# spio.net
KiCad netlist of a schematic drawn in EAGLE
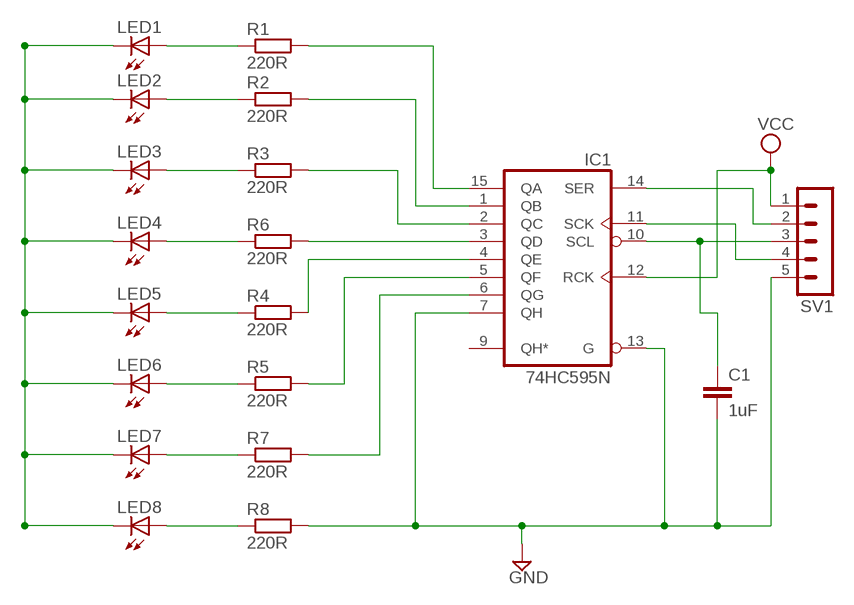
[diagram p0: schematic, sheet 1]

(export (version "E")
  (design (tool "Eeschema 10.0.6"))
  (components
    (comp (ref "C1")
      (value "1uF")
      (footprint "eagle-import:C025-024X044")
      (libsource (lib "eagle-import") (part "C-EU025-024X044"))
    )
    (comp (ref "IC1")
      (value "74HC595N")
      (footprint "eagle-import:DIL16")
      (libsource (lib "eagle-import") (part "74595NHC"))
    )
    (comp (ref "LED1")
      (value "LED5MM")
      (footprint "eagle-import:LED5MM")
      (libsource (lib "eagle-import") (part "LED5MM"))
    )
    (comp (ref "LED2")
      (value "LED5MM")
      (footprint "eagle-import:LED5MM")
      (libsource (lib "eagle-import") (part "LED5MM"))
    )
    (comp (ref "LED3")
      (value "LED5MM")
      (footprint "eagle-import:LED5MM")
      (libsource (lib "eagle-import") (part "LED5MM"))
    )
    (comp (ref "LED4")
      (value "LED5MM")
      (footprint "eagle-import:LED5MM")
      (libsource (lib "eagle-import") (part "LED5MM"))
    )
    (comp (ref "LED5")
      (value "LED5MM")
      (footprint "eagle-import:LED5MM")
      (libsource (lib "eagle-import") (part "LED5MM"))
    )
    (comp (ref "LED6")
      (value "LED5MM")
      (footprint "eagle-import:LED5MM")
      (libsource (lib "eagle-import") (part "LED5MM"))
    )
    (comp (ref "LED7")
      (value "LED5MM")
      (footprint "eagle-import:LED5MM")
      (libsource (lib "eagle-import") (part "LED5MM"))
    )
    (comp (ref "LED8")
      (value "LED5MM")
      (footprint "eagle-import:LED5MM")
      (libsource (lib "eagle-import") (part "LED5MM"))
    )
    (comp (ref "R1")
      (value "220R")
      (footprint "eagle-import:0204V")
      (libsource (lib "eagle-import") (part "R-EU_0204/2V"))
    )
    (comp (ref "R2")
      (value "220R")
      (footprint "eagle-import:0204V")
      (libsource (lib "eagle-import") (part "R-EU_0204/2V"))
    )
    (comp (ref "R3")
      (value "220R")
      (footprint "eagle-import:0204V")
      (libsource (lib "eagle-import") (part "R-EU_0204/2V"))
    )
    (comp (ref "R4")
      (value "220R")
      (footprint "eagle-import:0204V")
      (libsource (lib "eagle-import") (part "R-EU_0204/2V"))
    )
    (comp (ref "R5")
      (value "220R")
      (footprint "eagle-import:0204V")
      (libsource (lib "eagle-import") (part "R-EU_0204/2V"))
    )
    (comp (ref "R6")
      (value "220R")
      (footprint "eagle-import:0204V")
      (libsource (lib "eagle-import") (part "R-EU_0204/2V"))
    )
    (comp (ref "R7")
      (value "220R")
      (footprint "eagle-import:0204V")
      (libsource (lib "eagle-import") (part "R-EU_0204/2V"))
    )
    (comp (ref "R8")
      (value "220R")
      (footprint "eagle-import:0204V")
      (libsource (lib "eagle-import") (part "R-EU_0204/2V"))
    )
    (comp (ref "SV1")
      (value "MA05-1")
      (footprint "eagle-import:MA05-1")
      (libsource (lib "eagle-import") (part "MA05-1"))
    )
  )
  (nets
    (net (code "1") (name "GND") (class "Default")
      (node (ref "C1") (pin "2") (pinfunction "2_2") (pintype "passive"))
      (node (ref "IC1") (pin "13") (pinfunction "G_13") (pintype "input"))
      (node (ref "IC1") (pin "7") (pinfunction "QH_7") (pintype "tri_state"))
      (node (ref "R8") (pin "2") (pinfunction "2_2") (pintype "passive"))
      (node (ref "SV1") (pin "5") (pinfunction "5_5") (pintype "passive"))
    )
    (net (code "2") (name "Net-(IC1A-QA)") (class "Default")
      (node (ref "IC1") (pin "15") (pinfunction "QA_15") (pintype "tri_state"))
      (node (ref "R1") (pin "2") (pinfunction "2_2") (pintype "passive"))
    )
    (net (code "3") (name "Net-(IC1A-QB)") (class "Default")
      (node (ref "IC1") (pin "1") (pinfunction "QB_1") (pintype "tri_state"))
      (node (ref "R2") (pin "2") (pinfunction "2_2") (pintype "passive"))
    )
    (net (code "4") (name "Net-(IC1A-QC)") (class "Default")
      (node (ref "IC1") (pin "2") (pinfunction "QC_2") (pintype "tri_state"))
      (node (ref "R3") (pin "2") (pinfunction "2_2") (pintype "passive"))
    )
    (net (code "5") (name "Net-(IC1A-QD)") (class "Default")
      (node (ref "IC1") (pin "3") (pinfunction "QD_3") (pintype "tri_state"))
      (node (ref "R6") (pin "2") (pinfunction "2_2") (pintype "passive"))
    )
    (net (code "6") (name "Net-(IC1A-QE)") (class "Default")
      (node (ref "IC1") (pin "4") (pinfunction "QE_4") (pintype "tri_state"))
      (node (ref "R4") (pin "2") (pinfunction "2_2") (pintype "passive"))
    )
    (net (code "7") (name "Net-(IC1A-QF)") (class "Default")
      (node (ref "IC1") (pin "5") (pinfunction "QF_5") (pintype "tri_state"))
      (node (ref "R5") (pin "2") (pinfunction "2_2") (pintype "passive"))
    )
    (net (code "8") (name "Net-(IC1A-QG)") (class "Default")
      (node (ref "IC1") (pin "6") (pinfunction "QG_6") (pintype "tri_state"))
      (node (ref "R7") (pin "2") (pinfunction "2_2") (pintype "passive"))
    )
    (net (code "9") (name "Net-(IC1A-SCK)") (class "Default")
      (node (ref "IC1") (pin "11") (pinfunction "SCK_11") (pintype "input"))
      (node (ref "SV1") (pin "4") (pinfunction "4_4") (pintype "passive"))
    )
    (net (code "10") (name "Net-(IC1A-SCL)") (class "Default")
      (node (ref "C1") (pin "1") (pinfunction "1_1") (pintype "passive"))
      (node (ref "IC1") (pin "10") (pinfunction "SCL_10") (pintype "input"))
      (node (ref "SV1") (pin "3") (pinfunction "3_3") (pintype "passive"))
    )
    (net (code "11") (name "Net-(IC1A-SER)") (class "Default")
      (node (ref "IC1") (pin "14") (pinfunction "SER_14") (pintype "input"))
      (node (ref "SV1") (pin "2") (pinfunction "2_2") (pintype "passive"))
    )
    (net (code "12") (name "Net-(LED1-C)") (class "Default")
      (node (ref "LED1") (pin "K") (pinfunction "C_K") (pintype "passive"))
      (node (ref "LED2") (pin "K") (pinfunction "C_K") (pintype "passive"))
      (node (ref "LED3") (pin "K") (pinfunction "C_K") (pintype "passive"))
      (node (ref "LED4") (pin "K") (pinfunction "C_K") (pintype "passive"))
      (node (ref "LED5") (pin "K") (pinfunction "C_K") (pintype "passive"))
      (node (ref "LED6") (pin "K") (pinfunction "C_K") (pintype "passive"))
      (node (ref "LED7") (pin "K") (pinfunction "C_K") (pintype "passive"))
      (node (ref "LED8") (pin "K") (pinfunction "C_K") (pintype "passive"))
    )
    (net (code "13") (name "Net-(LED1-PadA)") (class "Default")
      (node (ref "LED1") (pin "A") (pinfunction "A_A") (pintype "passive"))
      (node (ref "R1") (pin "1") (pinfunction "1_1") (pintype "passive"))
    )
    (net (code "14") (name "Net-(LED2-PadA)") (class "Default")
      (node (ref "LED2") (pin "A") (pinfunction "A_A") (pintype "passive"))
      (node (ref "R2") (pin "1") (pinfunction "1_1") (pintype "passive"))
    )
    (net (code "15") (name "Net-(LED3-PadA)") (class "Default")
      (node (ref "LED3") (pin "A") (pinfunction "A_A") (pintype "passive"))
      (node (ref "R3") (pin "1") (pinfunction "1_1") (pintype "passive"))
    )
    (net (code "16") (name "Net-(LED4-PadA)") (class "Default")
      (node (ref "LED4") (pin "A") (pinfunction "A_A") (pintype "passive"))
      (node (ref "R6") (pin "1") (pinfunction "1_1") (pintype "passive"))
    )
    (net (code "17") (name "Net-(LED5-PadA)") (class "Default")
      (node (ref "LED5") (pin "A") (pinfunction "A_A") (pintype "passive"))
      (node (ref "R4") (pin "1") (pinfunction "1_1") (pintype "passive"))
    )
    (net (code "18") (name "Net-(LED6-PadA)") (class "Default")
      (node (ref "LED6") (pin "A") (pinfunction "A_A") (pintype "passive"))
      (node (ref "R5") (pin "1") (pinfunction "1_1") (pintype "passive"))
    )
    (net (code "19") (name "Net-(LED7-PadA)") (class "Default")
      (node (ref "LED7") (pin "A") (pinfunction "A_A") (pintype "passive"))
      (node (ref "R7") (pin "1") (pinfunction "1_1") (pintype "passive"))
    )
    (net (code "20") (name "Net-(LED8-PadA)") (class "Default")
      (node (ref "LED8") (pin "A") (pinfunction "A_A") (pintype "passive"))
      (node (ref "R8") (pin "1") (pinfunction "1_1") (pintype "passive"))
    )
    (net (code "21") (name "VCC") (class "Default")
      (node (ref "IC1") (pin "12") (pinfunction "RCK_12") (pintype "input"))
      (node (ref "SV1") (pin "1") (pinfunction "1_1") (pintype "passive"))
    )
    (net (code "22") (name "unconnected-(IC1A-QH*-Pad9)") (class "Default")
      (node (ref "IC1") (pin "9") (pinfunction "QH*_9") (pintype "tri_state"))
    )
  )
)
